# SparkFun_RTK_Express_Plus.net
KiCad netlist of a schematic drawn in EAGLE
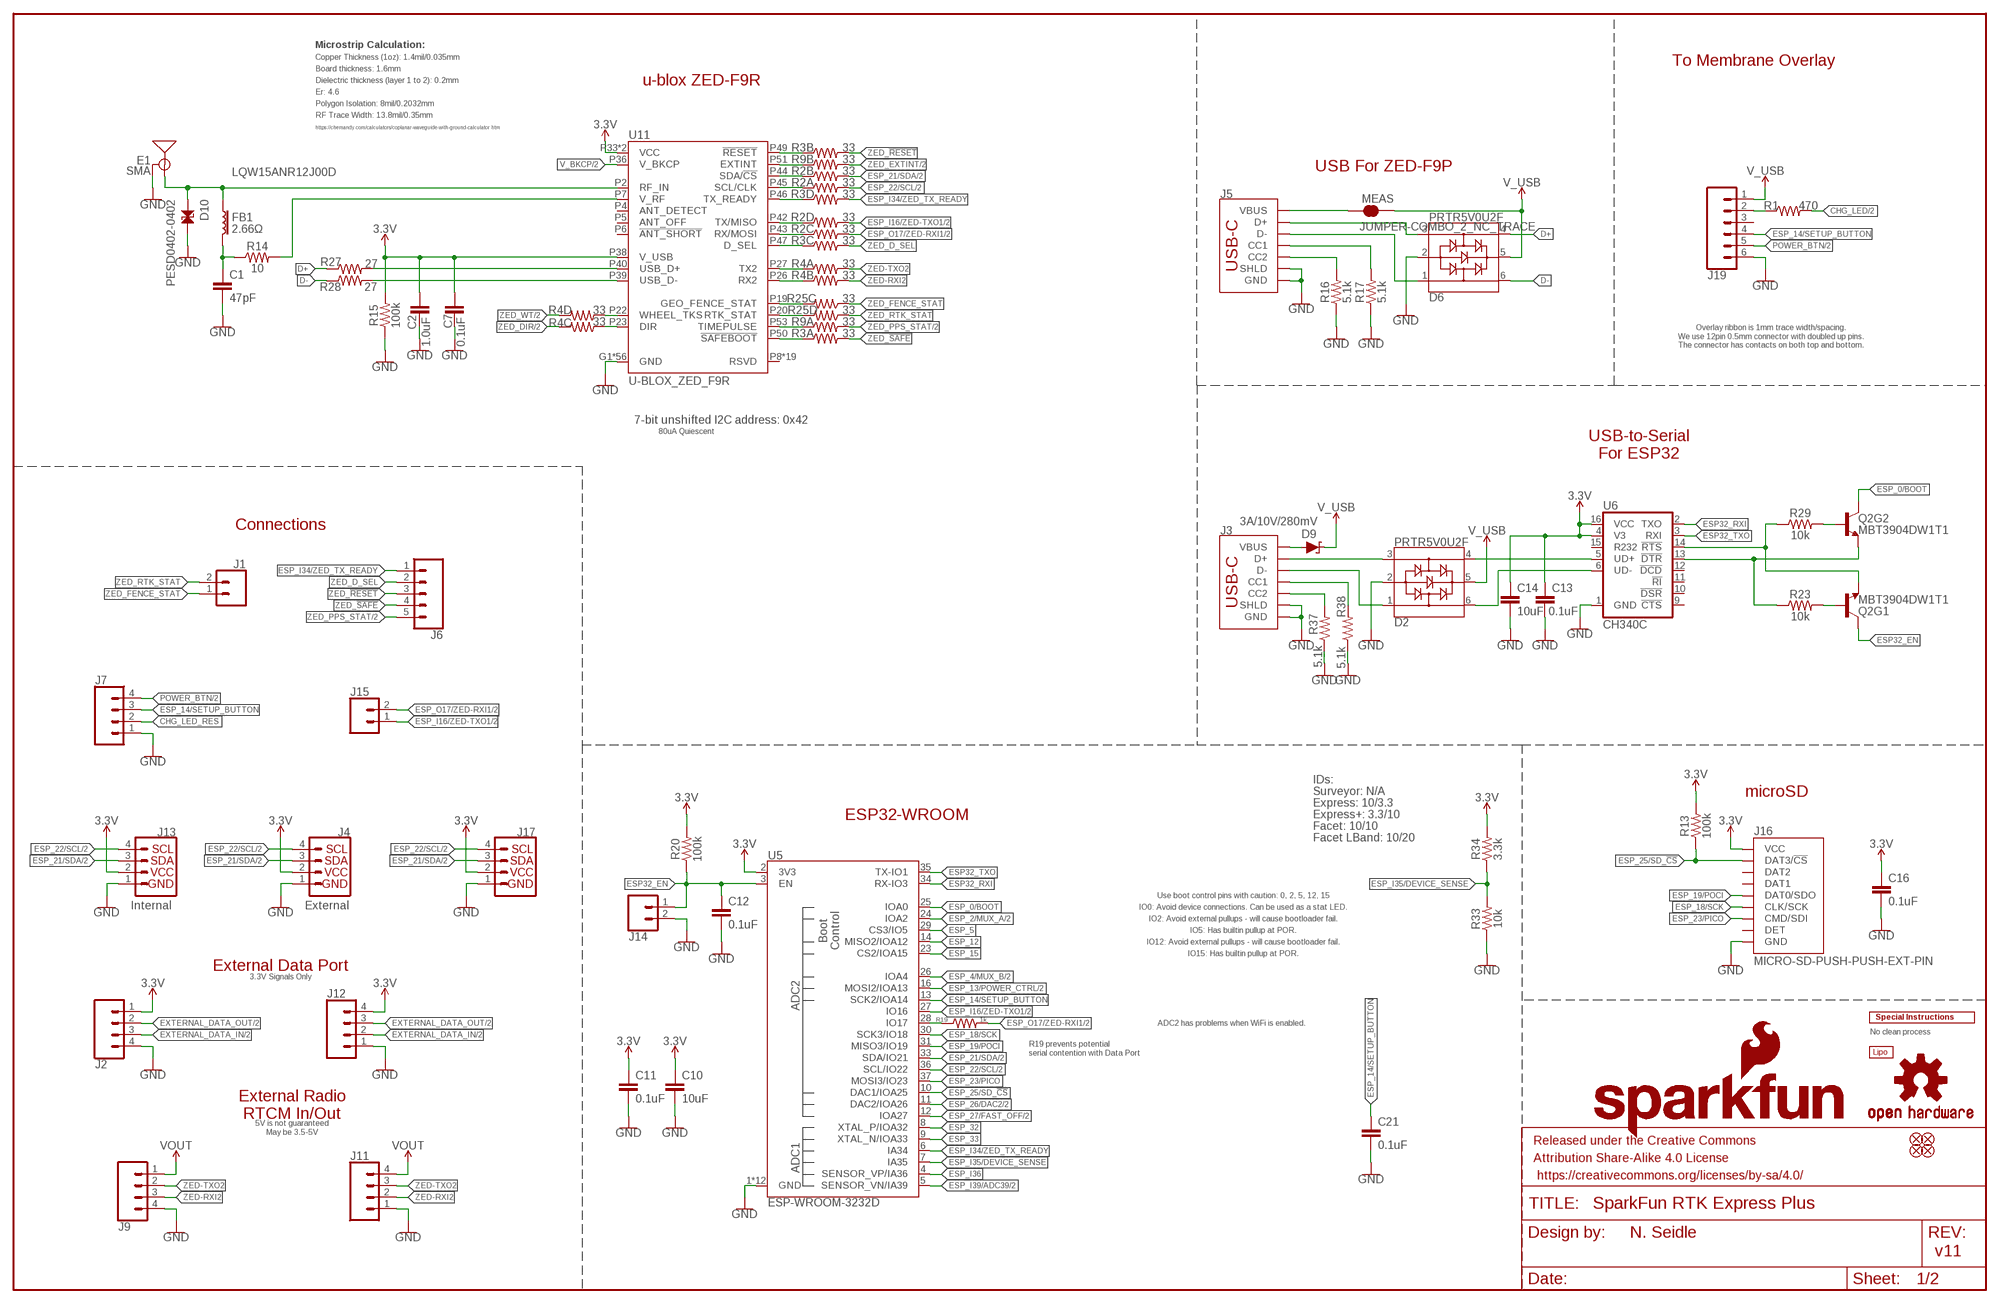
[diagram p0: schematic, sheet 1]
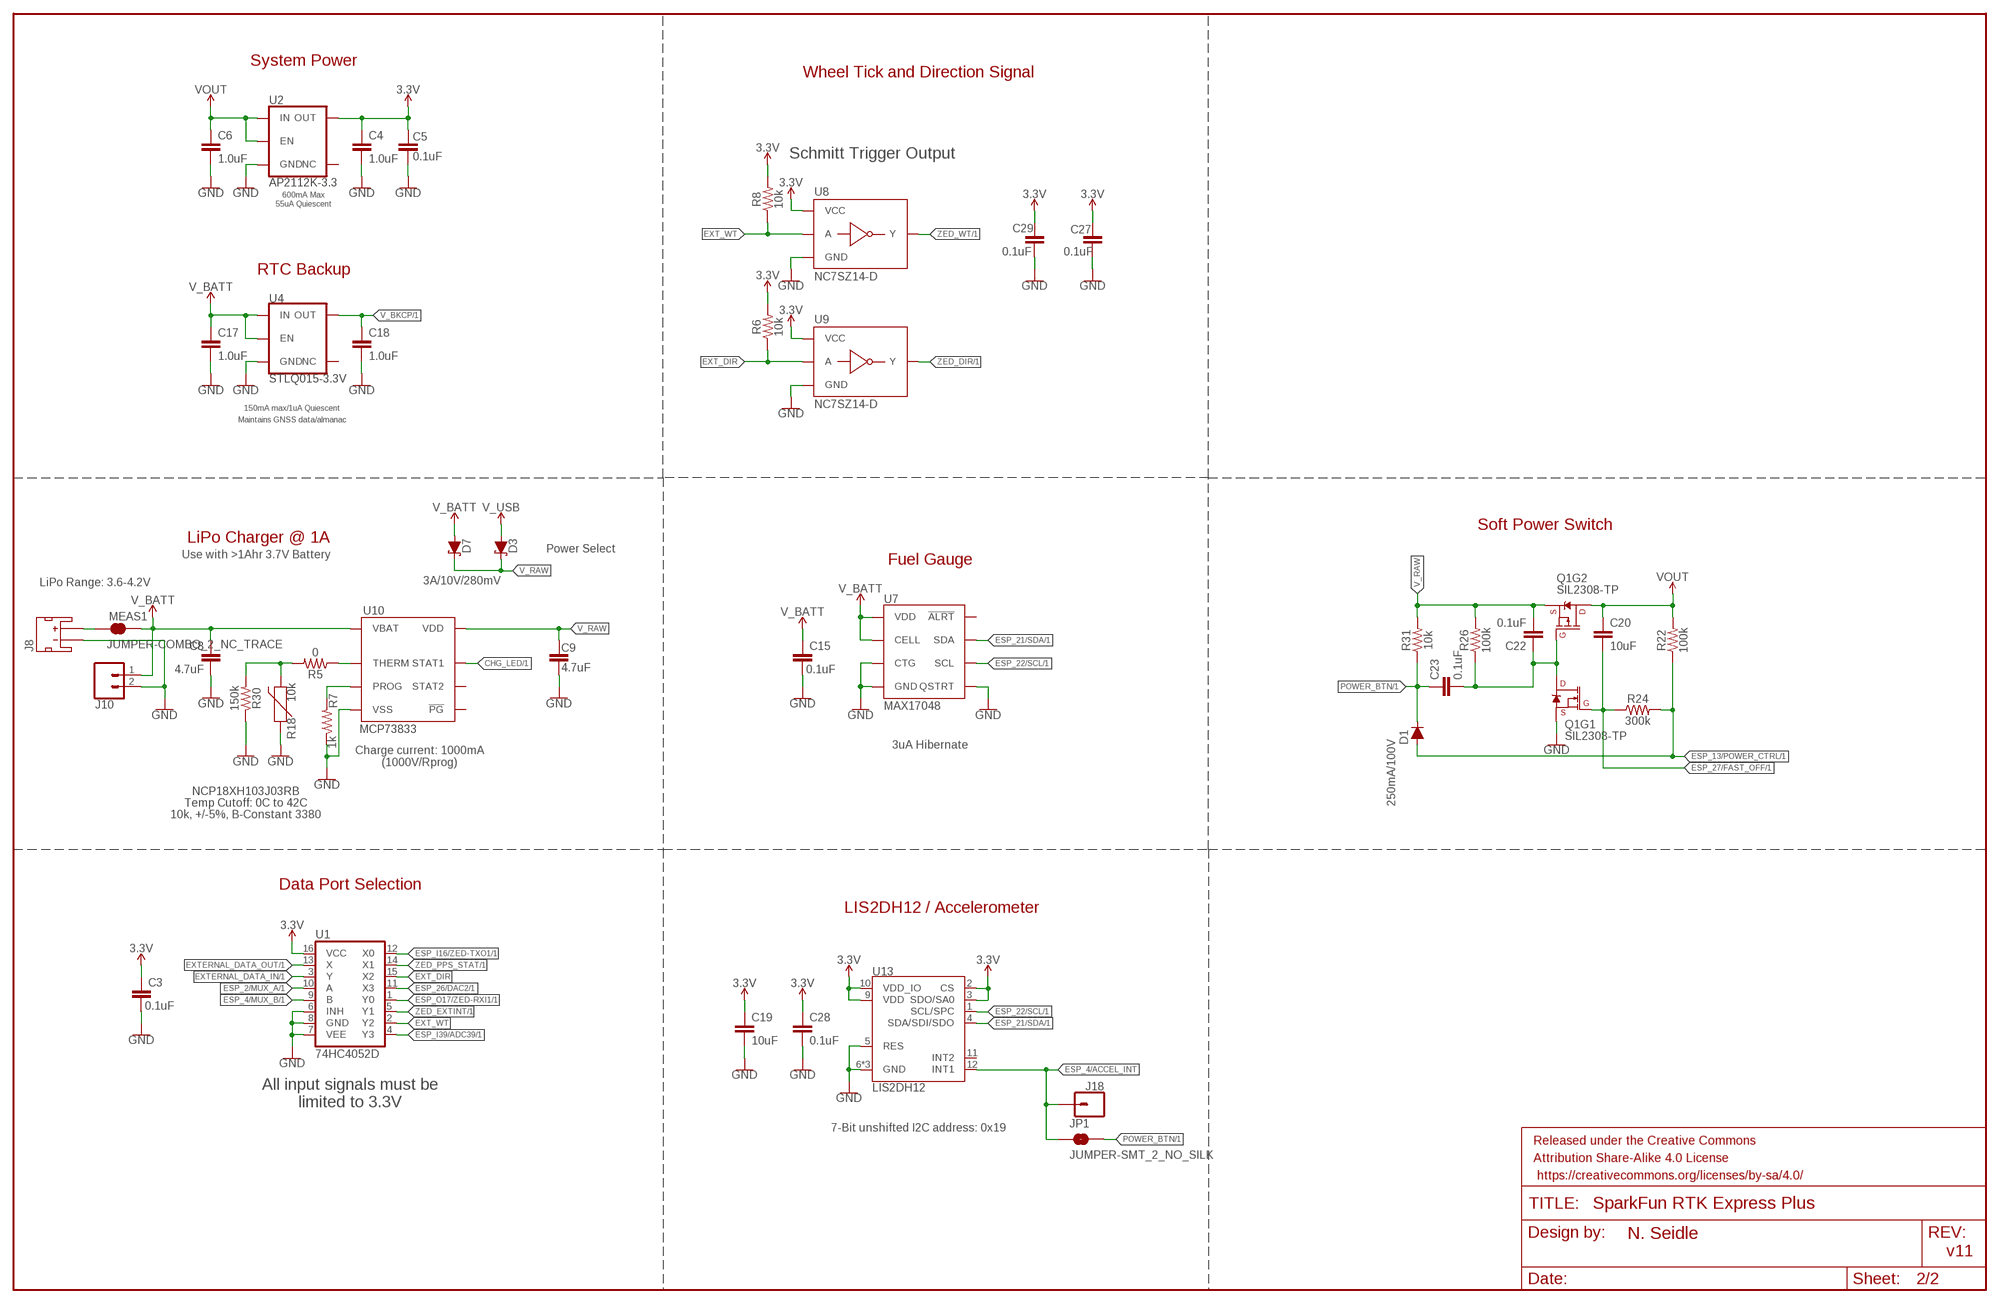
[diagram p1: schematic, sheet 2]

(export (version "E")
  (design (tool "Eeschema 10.0.6"))
  (components
    (comp (ref "C3")
      (value "0.1uF")
      (footprint "eagle-import:0603")
      (libsource (lib "eagle-import") (part "0.1UF-0603-25V-(+80/-20%)"))
    )
    (comp (ref "C4")
      (value "1.0uF")
      (footprint "eagle-import:0603")
      (libsource (lib "eagle-import") (part "1.0UF-0603-16V-10%-X7R"))
    )
    (comp (ref "C5")
      (value "0.1uF")
      (footprint "eagle-import:0603")
      (libsource (lib "eagle-import") (part "0.1UF-0603-25V-5%"))
    )
    (comp (ref "C6")
      (value "1.0uF")
      (footprint "eagle-import:0603")
      (libsource (lib "eagle-import") (part "1.0UF-0603-16V-10%-X7R"))
    )
    (comp (ref "C8")
      (value "4.7uF")
      (footprint "eagle-import:0603")
      (libsource (lib "eagle-import") (part "4.7UF-0603-35V-(20%)"))
    )
    (comp (ref "C9")
      (value "4.7uF")
      (footprint "eagle-import:0603")
      (libsource (lib "eagle-import") (part "4.7UF-0603-35V-(20%)"))
    )
    (comp (ref "C15")
      (value "0.1uF")
      (footprint "eagle-import:0603")
      (libsource (lib "eagle-import") (part "0.1UF-0603-25V-(+80/-20%)"))
    )
    (comp (ref "C17")
      (value "1.0uF")
      (footprint "eagle-import:0603")
      (libsource (lib "eagle-import") (part "1.0UF-0603-16V-10%-X7R"))
    )
    (comp (ref "C18")
      (value "1.0uF")
      (footprint "eagle-import:0603")
      (libsource (lib "eagle-import") (part "1.0UF-0603-16V-10%-X7R"))
    )
    (comp (ref "C19")
      (value "10uF")
      (footprint "eagle-import:0603")
      (libsource (lib "eagle-import") (part "10UF-0603-6.3V-20%"))
    )
    (comp (ref "C20")
      (value "10uF")
      (footprint "eagle-import:0603")
      (libsource (lib "eagle-import") (part "10UF-0603-6.3V-20%"))
    )
    (comp (ref "C22")
      (value "0.1uF")
      (footprint "eagle-import:0603")
      (libsource (lib "eagle-import") (part "0.1UF-0603-25V-5%"))
    )
    (comp (ref "C23")
      (value "0.1uF")
      (footprint "eagle-import:0603")
      (libsource (lib "eagle-import") (part "0.1UF-0603-25V-5%"))
    )
    (comp (ref "C27")
      (value "0.1uF")
      (footprint "eagle-import:0603")
      (libsource (lib "eagle-import") (part "0.1UF-0603-25V-(+80/-20%)"))
    )
    (comp (ref "C28")
      (value "0.1uF")
      (footprint "eagle-import:0603")
      (libsource (lib "eagle-import") (part "0.1UF-0603-25V-(+80/-20%)"))
    )
    (comp (ref "C29")
      (value "0.1uF")
      (footprint "eagle-import:0603")
      (libsource (lib "eagle-import") (part "0.1UF-0603-25V-(+80/-20%)"))
    )
    (comp (ref "D1")
      (value "250mA/100V")
      (footprint "eagle-import:SOD-323")
      (libsource (lib "eagle-import") (part "DIODE-BAS16J"))
    )
    (comp (ref "D3")
      (value "3A/10V/280mV")
      (footprint "eagle-import:SOD-323")
      (libsource (lib "eagle-import") (part "DIODE-SCHOTTKY-BAT60A"))
    )
    (comp (ref "D7")
      (value "3A/10V/280mV")
      (footprint "eagle-import:SOD-323")
      (libsource (lib "eagle-import") (part "DIODE-SCHOTTKY-BAT60A"))
    )
    (comp (ref "FRAME3")
      (value "FRAME-LEDGERNO_FOOTPRINT")
      (footprint "eagle-import:DUMMY")
      (fields (field (name "DESIGNER") "N. Seidle") (field (name "REV") "v10"))
      (libsource (lib "eagle-import") (part "FRAME-LEDGERNO_FOOTPRINT"))
    )
    (comp (ref "J8")
      (value "JST_2MM_MALE")
      (footprint "eagle-import:JST-2-SMD")
      (libsource (lib "eagle-import") (part "JST_2MM_MALE"))
    )
    (comp (ref "J10")
      (value "CONN_021X02_NO_SILK")
      (footprint "eagle-import:1X02_NO_SILK")
      (libsource (lib "eagle-import") (part "CONN_021X02_NO_SILK"))
    )
    (comp (ref "J18")
      (value "CONN_01PTH_NO_SILK_YES_STOP")
      (footprint "eagle-import:1X01_NO_SILK")
      (libsource (lib "eagle-import") (part "CONN_01PTH_NO_SILK_YES_STOP"))
    )
    (comp (ref "JP1")
      (value "JUMPER-SMT_2_NO_SILK")
      (footprint "eagle-import:SMT-JUMPER_2_NO_SILK")
      (libsource (lib "eagle-import") (part "JUMPER-SMT_2_NO_SILK"))
    )
    (comp (ref "MEAS1")
      (value "JUMPER-COMBO_2_NC_TRACE")
      (footprint "eagle-import:COMBO-JUMPER_2_NC_TRACE")
      (libsource (lib "eagle-import") (part "JUMPER-COMBO_2_NC_TRACE"))
    )
    (comp (ref "Q1")
      (value "SIL2308-TP")
      (footprint "eagle-import:SOT26")
      (libsource (lib "eagle-import") (part "MOSFET_COMPLIMENTARY_PAIR-SIL2308"))
    )
    (comp (ref "R5")
      (value "0")
      (footprint "eagle-import:0603")
      (libsource (lib "eagle-import") (part "0OHM-0603-1/10W"))
    )
    (comp (ref "R6")
      (value "10k")
      (footprint "eagle-import:0603")
      (libsource (lib "eagle-import") (part "10KOHM-0603-1/10W-1%"))
    )
    (comp (ref "R7")
      (value "1k")
      (footprint "eagle-import:0603")
      (libsource (lib "eagle-import") (part "1KOHM-0603-1/10W-1%"))
    )
    (comp (ref "R8")
      (value "10k")
      (footprint "eagle-import:0603")
      (libsource (lib "eagle-import") (part "10KOHM-0603-1/10W-1%"))
    )
    (comp (ref "R18")
      (value "10k")
      (footprint "eagle-import:0603")
      (libsource (lib "eagle-import") (part "NTC-THERMISTOR-0603"))
    )
    (comp (ref "R22")
      (value "100k")
      (footprint "eagle-import:0603")
      (libsource (lib "eagle-import") (part "100KOHM-0603-1/10W-1%"))
    )
    (comp (ref "R24")
      (value "300k")
      (footprint "eagle-import:0603")
      (libsource (lib "eagle-import") (part "300KOHM-0603-1/10W-1%"))
    )
    (comp (ref "R26")
      (value "100k")
      (footprint "eagle-import:0603")
      (libsource (lib "eagle-import") (part "100KOHM-0603-1/10W-1%"))
    )
    (comp (ref "R30")
      (value "150k")
      (footprint "eagle-import:0603")
      (libsource (lib "eagle-import") (part "150KOHM-0603-1/10W-1%"))
    )
    (comp (ref "R31")
      (value "10k")
      (footprint "eagle-import:0603")
      (libsource (lib "eagle-import") (part "10KOHM-0603-1/10W-1%"))
    )
    (comp (ref "U1")
      (value "74HC4052D")
      (footprint "eagle-import:SO16")
      (libsource (lib "eagle-import") (part "744052DHC"))
    )
    (comp (ref "U2")
      (value "AP2112K-3.3")
      (footprint "eagle-import:SOT23-5")
      (libsource (lib "eagle-import") (part "V_REG_AP2112K-3.3V"))
    )
    (comp (ref "U4")
      (value "STLQ015-3.3V")
      (footprint "eagle-import:SOT23-5")
      (libsource (lib "eagle-import") (part "STLQ015-3.3V"))
    )
    (comp (ref "U7")
      (value "MAX17048")
      (footprint "eagle-import:DFN-8")
      (libsource (lib "eagle-import") (part "MAX17048DFN8"))
    )
    (comp (ref "U8")
      (value "NC7SZ14-D")
      (footprint "eagle-import:SIP6")
      (libsource (lib "eagle-import") (part "UHS_INVERTER_SCHMITT_TRIGGERSIP6"))
    )
    (comp (ref "U9")
      (value "NC7SZ14-D")
      (footprint "eagle-import:SIP6")
      (libsource (lib "eagle-import") (part "UHS_INVERTER_SCHMITT_TRIGGERSIP6"))
    )
    (comp (ref "U10")
      (value "MCP73833")
      (footprint "eagle-import:DFN-10")
      (libsource (lib "eagle-import") (part "MCP73833"))
    )
    (comp (ref "U13")
      (value "LIS2DH12")
      (footprint "eagle-import:LGA-12-LISDH12")
      (libsource (lib "eagle-import") (part "LIS2DH12"))
    )
    (comp (ref "BT1")
      (value "LIPO-OUTLINE1000")
      (footprint "eagle-import:LIPO-1000")
      (libsource (lib "eagle-import") (part "LIPO-OUTLINE1000"))
    )
    (comp (ref "C1")
      (value "47pF")
      (footprint "eagle-import:0402")
      (libsource (lib "eagle-import") (part "47PF-0402-25V-5%-X7R"))
    )
    (comp (ref "C2")
      (value "1.0uF")
      (footprint "eagle-import:0603")
      (libsource (lib "eagle-import") (part "1.0UF-0603-16V-10%-X7R"))
    )
    (comp (ref "C7")
      (value "0.1uF")
      (footprint "eagle-import:0603")
      (libsource (lib "eagle-import") (part "0.1UF-0603-25V-5%"))
    )
    (comp (ref "C10")
      (value "10uF")
      (footprint "eagle-import:0603")
      (libsource (lib "eagle-import") (part "10UF-0603-6.3V-20%"))
    )
    (comp (ref "C11")
      (value "0.1uF")
      (footprint "eagle-import:0603")
      (libsource (lib "eagle-import") (part "0.1UF-0603-25V-(+80/-20%)"))
    )
    (comp (ref "C12")
      (value "0.1uF")
      (footprint "eagle-import:0603")
      (libsource (lib "eagle-import") (part "0.1UF-0603-25V-(+80/-20%)"))
    )
    (comp (ref "C13")
      (value "0.1uF")
      (footprint "eagle-import:0603")
      (libsource (lib "eagle-import") (part "0.1UF-0603-25V-(+80/-20%)"))
    )
    (comp (ref "C14")
      (value "10uF")
      (footprint "eagle-import:0603")
      (libsource (lib "eagle-import") (part "10UF-0603-6.3V-20%"))
    )
    (comp (ref "C16")
      (value "0.1uF")
      (footprint "eagle-import:0603")
      (libsource (lib "eagle-import") (part "0.1UF-0603-25V-(+80/-20%)"))
    )
    (comp (ref "C21")
      (value "0.1uF")
      (footprint "eagle-import:0603")
      (libsource (lib "eagle-import") (part "0.1UF-0603-25V-(+80/-20%)"))
    )
    (comp (ref "D2")
      (value "PRTR5V0U2F")
      (footprint "eagle-import:SOT886")
      (libsource (lib "eagle-import") (part "PRTR5V0U2F"))
    )
    (comp (ref "D6")
      (value "PRTR5V0U2F")
      (footprint "eagle-import:SOT886")
      (libsource (lib "eagle-import") (part "PRTR5V0U2F"))
    )
    (comp (ref "D9")
      (value "3A/10V/280mV")
      (footprint "eagle-import:SOD-323")
      (libsource (lib "eagle-import") (part "DIODE-SCHOTTKY-BAT60A"))
    )
    (comp (ref "D10")
      (value "PESD0402-0402")
      (footprint "eagle-import:0402")
      (fields
        (field (name "DIGIKEY_PART") "PESD0402-140CT-ND")
        (field (name "MOUSE_PART") "650-PESD0402-140")
      )
      (libsource (lib "eagle-import") (part "PESD0402-0402"))
    )
    (comp (ref "E1")
      (value "SMA")
      (footprint "eagle-import:SMA-EDGE")
      (libsource (lib "eagle-import") (part "ANTENNA-SMA-GROUNDEDEDGE_SMA"))
    )
    (comp (ref "FB1")
      (value "2.66Ω")
      (footprint "eagle-import:0402-TIGHT")
      (libsource (lib "eagle-import") (part "FERRITE_BEAD-0402-2.66Ω-1GHZ"))
    )
    (comp (ref "FRAME2")
      (value "FRAME-LEDGER")
      (footprint "eagle-import:CREATIVE_COMMONS")
      (libsource (lib "eagle-import") (part "FRAME-LEDGER"))
    )
    (comp (ref "J1")
      (value "CONN_021X02_NO_SILK")
      (footprint "eagle-import:1X02_NO_SILK")
      (libsource (lib "eagle-import") (part "CONN_021X02_NO_SILK"))
    )
    (comp (ref "J2")
      (value "CONN_04JST-SMD-LOCKING")
      (footprint "eagle-import:JST-4-SMD-1.25MM-LOCKING")
      (libsource (lib "eagle-import") (part "CONN_04JST-SMD-LOCKING"))
    )
    (comp (ref "J3")
      (value "USB Female Type C Connector")
      (footprint "eagle-import:USB-C-16P_4LAYER-PADS")
      (libsource (lib "eagle-import") (part "USB_C_4-LAYER_PADS"))
    )
    (comp (ref "J4")
      (value "External")
      (footprint "eagle-import:JST04_1MM_RA")
      (libsource (lib "eagle-import") (part "I2C_STANDARDQWIIC"))
    )
    (comp (ref "J5")
      (value "USB Female Type C Connector")
      (footprint "eagle-import:USB-C-16P_4LAYER-PADS")
      (libsource (lib "eagle-import") (part "USB_C_4-LAYER_PADS"))
    )
    (comp (ref "J6")
      (value "CONN_05NO_SILK")
      (footprint "eagle-import:1X05_NO_SILK")
      (libsource (lib "eagle-import") (part "CONN_05NO_SILK"))
    )
    (comp (ref "J7")
      (value "CONN_041X04_NO_SILK_NO_POP")
      (footprint "eagle-import:1X04_NO_SILK")
      (libsource (lib "eagle-import") (part "CONN_041X04_NO_SILK_NO_POP"))
    )
    (comp (ref "J9")
      (value "CONN_04JST-SMD-LOCKING")
      (footprint "eagle-import:JST-4-SMD-1.25MM-LOCKING")
      (libsource (lib "eagle-import") (part "CONN_04JST-SMD-LOCKING"))
    )
    (comp (ref "J11")
      (value "CONN_041X04_NO_SILK_NO_POP")
      (footprint "eagle-import:1X04_NO_SILK")
      (libsource (lib "eagle-import") (part "CONN_041X04_NO_SILK_NO_POP"))
    )
    (comp (ref "J12")
      (value "CONN_041X04_NO_SILK_NO_POP")
      (footprint "eagle-import:1X04_NO_SILK")
      (libsource (lib "eagle-import") (part "CONN_041X04_NO_SILK_NO_POP"))
    )
    (comp (ref "J13")
      (value "Internal")
      (footprint "eagle-import:JST04_1MM_RA")
      (libsource (lib "eagle-import") (part "I2C_STANDARDQWIIC"))
    )
    (comp (ref "J14")
      (value "CONN_021X02_NO_SILK")
      (footprint "eagle-import:1X02_NO_SILK")
      (libsource (lib "eagle-import") (part "CONN_021X02_NO_SILK"))
    )
    (comp (ref "J15")
      (value "CONN_021X02_NO_SILK")
      (footprint "eagle-import:1X02_NO_SILK")
      (libsource (lib "eagle-import") (part "CONN_021X02_NO_SILK"))
    )
    (comp (ref "J16")
      (value "MICRO-SD-PUSH-PUSH-EXT-PIN")
      (footprint "eagle-import:MICROSD-EXTERNALPIN")
      (libsource (lib "eagle-import") (part "MICRO-SD-PUSH-PUSH-EXT-PIN"))
    )
    (comp (ref "J17")
      (value "Qwiic Right Angle")
      (footprint "eagle-import:1X04_NO_SILK")
      (libsource (lib "eagle-import") (part "I2C_STANDARD_NO_SILK"))
    )
    (comp (ref "J19")
      (value "CONN_061MM-LIF")
      (footprint "eagle-import:FPC_6_1MM-LIF")
      (libsource (lib "eagle-import") (part "CONN_061MM-LIF"))
    )
    (comp (ref "JP21")
      (value "FIDUCIALUFIDUCIAL")
      (footprint "eagle-import:FIDUCIAL-MICRO")
      (libsource (lib "eagle-import") (part "FIDUCIALUFIDUCIAL"))
    )
    (comp (ref "JP61")
      (value "FIDUCIALUFIDUCIAL")
      (footprint "eagle-import:FIDUCIAL-MICRO")
      (libsource (lib "eagle-import") (part "FIDUCIALUFIDUCIAL"))
    )
    (comp (ref "JP71")
      (value "FIDUCIALUFIDUCIAL")
      (footprint "eagle-import:FIDUCIAL-MICRO")
      (libsource (lib "eagle-import") (part "FIDUCIALUFIDUCIAL"))
    )
    (comp (ref "JP81")
      (value "FIDUCIALUFIDUCIAL")
      (footprint "eagle-import:FIDUCIAL-MICRO")
      (libsource (lib "eagle-import") (part "FIDUCIALUFIDUCIAL"))
    )
    (comp (ref "LOGO1")
      (value "OSHW-LOGOMINI")
      (footprint "eagle-import:OSHW-LOGO-MINI")
      (libsource (lib "eagle-import") (part "OSHW-LOGOMINI"))
    )
    (comp (ref "LOGO2")
      (value "SFE_LOGO_NAME_FLAME.1_INCH")
      (footprint "eagle-import:SFE_LOGO_NAME_FLAME_.1")
      (libsource (lib "eagle-import") (part "SFE_LOGO_NAME_FLAME.1_INCH"))
    )
    (comp (ref "MEAS")
      (value "JUMPER-COMBO_2_NC_TRACE")
      (footprint "eagle-import:COMBO-JUMPER_2_NC_TRACE")
      (libsource (lib "eagle-import") (part "JUMPER-COMBO_2_NC_TRACE"))
    )
    (comp (ref "Q2")
      (value "MBT3904DW1T1")
      (footprint "eagle-import:SC70-6")
      (libsource (lib "eagle-import") (part "TRANS_NPN_DUAL-MBT3904DW1T1"))
    )
    (comp (ref "R1")
      (value "470")
      (footprint "eagle-import:0603")
      (libsource (lib "eagle-import") (part "470OHM-0603-1/10W-1%"))
    )
    (comp (ref "R2")
      (value "33")
      (footprint "eagle-import:1206_RA")
      (libsource (lib "eagle-import") (part "33OHM_RA-1206-1/16W-5%"))
    )
    (comp (ref "R3")
      (value "33")
      (footprint "eagle-import:1206_RA")
      (libsource (lib "eagle-import") (part "33OHM_RA-1206-1/16W-5%"))
    )
    (comp (ref "R4")
      (value "33")
      (footprint "eagle-import:1206_RA")
      (libsource (lib "eagle-import") (part "33OHM_RA-1206-1/16W-5%"))
    )
    (comp (ref "R9")
      (value "33")
      (footprint "eagle-import:1206_RA")
      (libsource (lib "eagle-import") (part "33OHM_RA-1206-1/16W-5%"))
    )
    (comp (ref "R13")
      (value "100k")
      (footprint "eagle-import:0603")
      (libsource (lib "eagle-import") (part "100KOHM-0603-1/10W-1%"))
    )
    (comp (ref "R14")
      (value "10")
      (footprint "eagle-import:0603")
      (libsource (lib "eagle-import") (part "10OHM-0603-1/10W-1%"))
    )
    (comp (ref "R15")
      (value "100k")
      (footprint "eagle-import:0603")
      (libsource (lib "eagle-import") (part "100KOHM-0603-1/10W-1%"))
    )
    (comp (ref "R16")
      (value "5.1k")
      (footprint "eagle-import:0603")
      (libsource (lib "eagle-import") (part "5.1KOHM5.1KOHM-0603-1/10W-1%"))
    )
    (comp (ref "R17")
      (value "5.1k")
      (footprint "eagle-import:0603")
      (libsource (lib "eagle-import") (part "5.1KOHM5.1KOHM-0603-1/10W-1%"))
    )
    (comp (ref "R19")
      (value "1k")
      (footprint "eagle-import:0603")
      (libsource (lib "eagle-import") (part "1KOHM-0603-1/10W-1%"))
    )
    (comp (ref "R20")
      (value "100k")
      (footprint "eagle-import:0603")
      (libsource (lib "eagle-import") (part "100KOHM-0603-1/10W-1%"))
    )
    (comp (ref "R23")
      (value "10k")
      (footprint "eagle-import:0603")
      (libsource (lib "eagle-import") (part "10KOHM-0603-1/10W-1%"))
    )
    (comp (ref "R25")
      (value "33")
      (footprint "eagle-import:1206_RA")
      (libsource (lib "eagle-import") (part "33OHM_RA-1206-1/16W-5%"))
    )
    (comp (ref "R27")
      (value "27")
      (footprint "eagle-import:0603")
      (libsource (lib "eagle-import") (part "27OHM-0603-1/10W-1%"))
    )
    (comp (ref "R28")
      (value "27")
      (footprint "eagle-import:0603")
      (libsource (lib "eagle-import") (part "27OHM-0603-1/10W-1%"))
    )
    (comp (ref "R29")
      (value "10k")
      (footprint "eagle-import:0603")
      (libsource (lib "eagle-import") (part "10KOHM-0603-1/10W-1%"))
    )
    (comp (ref "R33")
      (value "10k")
      (footprint "eagle-import:0603")
      (libsource (lib "eagle-import") (part "10KOHM-0603-1/10W-1%"))
    )
    (comp (ref "R34")
      (value "3.3k")
      (footprint "eagle-import:0603")
      (libsource (lib "eagle-import") (part "3.3KOHM-0603-1/10W-1%"))
    )
    (comp (ref "R37")
      (value "5.1k")
      (footprint "eagle-import:0603")
      (libsource (lib "eagle-import") (part "5.1KOHM5.1KOHM-0603-1/10W-1%"))
    )
    (comp (ref "R38")
      (value "5.1k")
      (footprint "eagle-import:0603")
      (libsource (lib "eagle-import") (part "5.1KOHM5.1KOHM-0603-1/10W-1%"))
    )
    (comp (ref "U$2")
      (value "SPECIAL_INSTRUCTIONS-ORDERING")
      (footprint "eagle-import:ORDERING_INSTRUCTIONS")
      (libsource (lib "eagle-import") (part "SPECIAL_INSTRUCTIONS-ORDERING"))
    )
    (comp (ref "U5")
      (value "ESP-WROOM-3232D")
      (footprint "eagle-import:ESP-WROOM-32D")
      (libsource (lib "eagle-import") (part "ESP-WROOM-3232D"))
    )
    (comp (ref "U6")
      (value "CH340C")
      (footprint "eagle-import:SO016")
      (libsource (lib "eagle-import") (part "CH340C"))
    )
    (comp (ref "U11")
      (value "U-BLOX_ZED_F9R")
      (footprint "eagle-import:UBLOX_ZED_F9R")
      (libsource (lib "eagle-import") (part "U-BLOX_ZED_F9R"))
    )
  )
  (nets
    (net (code "1") (name "3.3V") (class "Default")
      (node (ref "C10") (pin "1") (pinfunction "1_1") (pintype "passive"))
      (node (ref "C11") (pin "1") (pinfunction "1_1") (pintype "passive"))
      (node (ref "C13") (pin "1") (pinfunction "1_1") (pintype "passive"))
      (node (ref "C14") (pin "1") (pinfunction "1_1") (pintype "passive"))
      (node (ref "C16") (pin "1") (pinfunction "1_1") (pintype "passive"))
      (node (ref "C19") (pin "1") (pinfunction "1_1") (pintype "passive"))
      (node (ref "C2") (pin "1") (pinfunction "1_1") (pintype "passive"))
      (node (ref "C27") (pin "1") (pinfunction "1_1") (pintype "passive"))
      (node (ref "C28") (pin "1") (pinfunction "1_1") (pintype "passive"))
      (node (ref "C29") (pin "1") (pinfunction "1_1") (pintype "passive"))
      (node (ref "C3") (pin "1") (pinfunction "1_1") (pintype "passive"))
      (node (ref "C4") (pin "1") (pinfunction "1_1") (pintype "passive"))
      (node (ref "C5") (pin "2") (pinfunction "2_2") (pintype "passive"))
      (node (ref "C7") (pin "2") (pinfunction "2_2") (pintype "passive"))
      (node (ref "J12") (pin "4") (pinfunction "4_4") (pintype "passive"))
      (node (ref "J13") (pin "2") (pinfunction "2_2") (pintype "power_in"))
      (node (ref "J16") (pin "4") (pinfunction "VCC_4") (pintype "bidirectional"))
      (node (ref "J17") (pin "2") (pinfunction "2_2") (pintype "power_in"))
      (node (ref "J2") (pin "1") (pinfunction "1_1") (pintype "passive"))
      (node (ref "J4") (pin "2") (pinfunction "2_2") (pintype "power_in"))
      (node (ref "R13") (pin "2") (pinfunction "2_2") (pintype "passive"))
      (node (ref "R15") (pin "2") (pinfunction "2_2") (pintype "passive"))
      (node (ref "R20") (pin "2") (pinfunction "2_2") (pintype "passive"))
      (node (ref "R34") (pin "2") (pinfunction "2_2") (pintype "passive"))
      (node (ref "R6") (pin "2") (pinfunction "2_2") (pintype "passive"))
      (node (ref "R8") (pin "2") (pinfunction "2_2") (pintype "passive"))
      (node (ref "U1") (pin "16") (pinfunction "VCC_16") (pintype "power_in"))
      (node (ref "U11") (pin "P33") (pinfunction "VCC_P33") (pintype "power_in"))
      (node (ref "U11") (pin "P34") (pinfunction "VCC_P34") (pintype "power_in"))
      (node (ref "U11") (pin "P38") (pinfunction "V_USB_P38") (pintype "power_in"))
      (node (ref "U13") (pin "10") (pinfunction "VDD_IO_10") (pintype "bidirectional"))
      (node (ref "U13") (pin "2") (pinfunction "CS_2") (pintype "bidirectional"))
      (node (ref "U13") (pin "3") (pinfunction "SDO/SA0_3") (pintype "bidirectional"))
      (node (ref "U13") (pin "9") (pinfunction "VDD_9") (pintype "bidirectional"))
      (node (ref "U2") (pin "5") (pinfunction "OUT_5") (pintype "passive"))
      (node (ref "U5") (pin "2") (pinfunction "3V3_2") (pintype "bidirectional"))
      (node (ref "U6") (pin "16") (pinfunction "VCC_16") (pintype "bidirectional"))
      (node (ref "U6") (pin "4") (pinfunction "V3_4") (pintype "bidirectional"))
      (node (ref "U8") (pin "P6") (pinfunction "VCC_P6") (pintype "power_in"))
      (node (ref "U9") (pin "P6") (pinfunction "VCC_P6") (pintype "power_in"))
    )
    (net (code "2") (name "CHG_LED") (class "Default")
      (node (ref "R1") (pin "2") (pinfunction "2_2") (pintype "passive"))
      (node (ref "U10") (pin "3") (pinfunction "STAT1_3") (pintype "bidirectional"))
    )
    (net (code "3") (name "CHG_LED_RES") (class "Default")
      (node (ref "J19") (pin "2") (pinfunction "2_2") (pintype "passive"))
      (node (ref "J7") (pin "2") (pinfunction "2_2") (pintype "passive"))
      (node (ref "R1") (pin "1") (pinfunction "1_1") (pintype "passive"))
    )
    (net (code "4") (name "D+") (class "Default")
      (node (ref "D6") (pin "4") (pinfunction "4_4") (pintype "bidirectional"))
      (node (ref "R27") (pin "1") (pinfunction "1_1") (pintype "passive"))
    )
    (net (code "5") (name "D-") (class "Default")
      (node (ref "D6") (pin "6") (pinfunction "6_6") (pintype "bidirectional"))
      (node (ref "R28") (pin "1") (pinfunction "1_1") (pintype "passive"))
    )
    (net (code "6") (name "ESP32_EN") (class "Default")
      (node (ref "C12") (pin "1") (pinfunction "1_1") (pintype "passive"))
      (node (ref "J14") (pin "1") (pinfunction "1_1") (pintype "passive"))
      (node (ref "Q2") (pin "3") (pinfunction "C_3") (pintype "passive"))
      (node (ref "R20") (pin "1") (pinfunction "1_1") (pintype "passive"))
      (node (ref "U5") (pin "3") (pinfunction "EN_3") (pintype "bidirectional"))
    )
    (net (code "7") (name "ESP32_RXI") (class "Default")
      (node (ref "U5") (pin "34") (pinfunction "RX-IO3_34") (pintype "bidirectional"))
      (node (ref "U6") (pin "2") (pinfunction "TXO_2") (pintype "bidirectional"))
    )
    (net (code "8") (name "ESP32_TXO") (class "Default")
      (node (ref "U5") (pin "35") (pinfunction "TX-IO1_35") (pintype "bidirectional"))
      (node (ref "U6") (pin "3") (pinfunction "RXI_3") (pintype "bidirectional"))
    )
    (net (code "9") (name "ESP_0{slash}BOOT") (class "Default")
      (node (ref "Q2") (pin "6") (pinfunction "C_6") (pintype "passive"))
      (node (ref "U5") (pin "25") (pinfunction "IOA0_25") (pintype "bidirectional"))
    )
    (net (code "10") (name "ESP_2{slash}MUX_A") (class "Default")
      (node (ref "U1") (pin "10") (pinfunction "A_10") (pintype "input"))
      (node (ref "U5") (pin "24") (pinfunction "IOA2_24") (pintype "bidirectional"))
    )
    (net (code "11") (name "ESP_4{slash}ACCEL_INT") (class "Default")
      (node (ref "J18") (pin "1") (pinfunction "1_1") (pintype "passive"))
      (node (ref "JP1") (pin "1") (pinfunction "1_1") (pintype "passive"))
      (node (ref "U13") (pin "12") (pinfunction "INT1_12") (pintype "bidirectional"))
    )
    (net (code "12") (name "ESP_4{slash}MUX_B") (class "Default")
      (node (ref "U1") (pin "9") (pinfunction "B_9") (pintype "input"))
      (node (ref "U5") (pin "26") (pinfunction "IOA4_26") (pintype "bidirectional"))
    )
    (net (code "13") (name "ESP_5") (class "Default")
      (node (ref "U5") (pin "29") (pinfunction "CS3/IO5_29") (pintype "bidirectional"))
    )
    (net (code "14") (name "ESP_12") (class "Default")
      (node (ref "U5") (pin "14") (pinfunction "MISO2/IOA12_14") (pintype "bidirectional"))
    )
    (net (code "15") (name "ESP_13{slash}POWER_CTRL") (class "Default")
      (node (ref "D1") (pin "A") (pinfunction "A_A") (pintype "passive"))
      (node (ref "R22") (pin "1") (pinfunction "1_1") (pintype "passive"))
      (node (ref "R24") (pin "2") (pinfunction "2_2") (pintype "passive"))
      (node (ref "U5") (pin "16") (pinfunction "MOSI2/IOA13_16") (pintype "bidirectional"))
    )
    (net (code "16") (name "ESP_14{slash}SETUP_BUTTON") (class "Default")
      (node (ref "C21") (pin "1") (pinfunction "1_1") (pintype "passive"))
      (node (ref "J19") (pin "4") (pinfunction "4_4") (pintype "passive"))
      (node (ref "J7") (pin "3") (pinfunction "3_3") (pintype "passive"))
      (node (ref "U5") (pin "13") (pinfunction "SCK2/IOA14_13") (pintype "bidirectional"))
    )
    (net (code "17") (name "ESP_15") (class "Default")
      (node (ref "U5") (pin "23") (pinfunction "CS2/IOA15_23") (pintype "bidirectional"))
    )
    (net (code "18") (name "ESP_18{slash}SCK") (class "Default")
      (node (ref "J16") (pin "5") (pinfunction "CLK/SCK_5") (pintype "bidirectional"))
      (node (ref "U5") (pin "30") (pinfunction "SCK3/IO18_30") (pintype "bidirectional"))
    )
    (net (code "19") (name "ESP_19{slash}POCI") (class "Default")
      (node (ref "J16") (pin "7") (pinfunction "DAT0/SDO_7") (pintype "bidirectional"))
      (node (ref "U5") (pin "31") (pinfunction "MISO3/IO19_31") (pintype "bidirectional"))
    )
    (net (code "20") (name "ESP_21{slash}SDA") (class "Default")
      (node (ref "J13") (pin "3") (pinfunction "3_3") (pintype "passive"))
      (node (ref "J17") (pin "3") (pinfunction "3_3") (pintype "passive"))
      (node (ref "J4") (pin "3") (pinfunction "3_3") (pintype "passive"))
      (node (ref "R2") (pin "P7") (pinfunction "2_P7") (pintype "passive"))
      (node (ref "U13") (pin "4") (pinfunction "SDA/SDI/SDO_4") (pintype "bidirectional"))
      (node (ref "U5") (pin "33") (pinfunction "SDA/IO21_33") (pintype "bidirectional"))
      (node (ref "U7") (pin "8") (pinfunction "SDA_8") (pintype "input"))
    )
    (net (code "21") (name "ESP_22{slash}SCL") (class "Default")
      (node (ref "J13") (pin "4") (pinfunction "4_4") (pintype "passive"))
      (node (ref "J17") (pin "4") (pinfunction "4_4") (pintype "passive"))
      (node (ref "J4") (pin "4") (pinfunction "4_4") (pintype "passive"))
      (node (ref "R2") (pin "P8") (pinfunction "2_P8") (pintype "passive"))
      (node (ref "U13") (pin "1") (pinfunction "SCL/SPC_1") (pintype "bidirectional"))
      (node (ref "U5") (pin "36") (pinfunction "SCL/IO22_36") (pintype "bidirectional"))
      (node (ref "U7") (pin "7") (pinfunction "SCL_7") (pintype "output"))
    )
    (net (code "22") (name "ESP_23{slash}PICO") (class "Default")
      (node (ref "J16") (pin "3") (pinfunction "CMD/SDI_3") (pintype "bidirectional"))
      (node (ref "U5") (pin "37") (pinfunction "MOSI3/IO23_37") (pintype "bidirectional"))
    )
    (net (code "23") (name "ESP_25{slash}SD_~{CS}") (class "Default")
      (node (ref "J16") (pin "2") (pinfunction "DAT3/~{CS}_2") (pintype "bidirectional"))
      (node (ref "R13") (pin "1") (pinfunction "1_1") (pintype "passive"))
      (node (ref "U5") (pin "10") (pinfunction "DAC1/IOA25_10") (pintype "bidirectional"))
    )
    (net (code "24") (name "ESP_26{slash}DAC2") (class "Default")
      (node (ref "U1") (pin "11") (pinfunction "X3_11") (pintype "bidirectional"))
      (node (ref "U5") (pin "11") (pinfunction "DAC2/IOA26_11") (pintype "bidirectional"))
    )
    (net (code "25") (name "ESP_27{slash}FAST_OFF") (class "Default")
      (node (ref "C20") (pin "2") (pinfunction "2_2") (pintype "passive"))
      (node (ref "Q1") (pin "G1") (pinfunction "G_G1") (pintype "bidirectional"))
      (node (ref "R24") (pin "1") (pinfunction "1_1") (pintype "passive"))
      (node (ref "U5") (pin "12") (pinfunction "IOA27_12") (pintype "bidirectional"))
    )
    (net (code "26") (name "ESP_32") (class "Default")
      (node (ref "U5") (pin "8") (pinfunction "XTAL_P/IOA32_8") (pintype "bidirectional"))
    )
    (net (code "27") (name "ESP_33") (class "Default")
      (node (ref "U5") (pin "9") (pinfunction "XTAL_N/IOA33_9") (pintype "bidirectional"))
    )
    (net (code "28") (name "ESP_I16{slash}ZED-TXO1") (class "Default")
      (node (ref "J15") (pin "1") (pinfunction "1_1") (pintype "passive"))
      (node (ref "R2") (pin "P5") (pinfunction "2_P5") (pintype "passive"))
      (node (ref "U1") (pin "12") (pinfunction "X0_12") (pintype "bidirectional"))
      (node (ref "U5") (pin "27") (pinfunction "IO16_27") (pintype "bidirectional"))
    )
    (net (code "29") (name "ESP_I34{slash}ZED_TX_READY") (class "Default")
      (node (ref "J6") (pin "1") (pinfunction "1_1") (pintype "passive"))
      (node (ref "R3") (pin "P5") (pinfunction "2_P5") (pintype "passive"))
      (node (ref "U5") (pin "6") (pinfunction "IA34_6") (pintype "bidirectional"))
    )
    (net (code "30") (name "ESP_I35{slash}DEVICE_SENSE") (class "Default")
      (node (ref "R33") (pin "2") (pinfunction "2_2") (pintype "passive"))
      (node (ref "R34") (pin "1") (pinfunction "1_1") (pintype "passive"))
      (node (ref "U5") (pin "7") (pinfunction "IA35_7") (pintype "bidirectional"))
    )
    (net (code "31") (name "ESP_I36") (class "Default")
      (node (ref "U5") (pin "4") (pinfunction "SENSOR_VP/IA36_4") (pintype "bidirectional"))
    )
    (net (code "32") (name "ESP_I39{slash}ADC39") (class "Default")
      (node (ref "U1") (pin "4") (pinfunction "Y3_4") (pintype "bidirectional"))
      (node (ref "U5") (pin "5") (pinfunction "SENSOR_VN/IA39_5") (pintype "bidirectional"))
    )
    (net (code "33") (name "ESP_O17{slash}ZED-RXI1") (class "Default")
      (node (ref "J15") (pin "2") (pinfunction "2_2") (pintype "passive"))
      (node (ref "R19") (pin "2") (pinfunction "2_2") (pintype "passive"))
      (node (ref "R2") (pin "P6") (pinfunction "2_P6") (pintype "passive"))
      (node (ref "U1") (pin "1") (pinfunction "Y0_1") (pintype "bidirectional"))
    )
    (net (code "34") (name "EXTERNAL_DATA_IN") (class "Default")
      (node (ref "J12") (pin "2") (pinfunction "2_2") (pintype "passive"))
      (node (ref "J2") (pin "3") (pinfunction "3_3") (pintype "passive"))
      (node (ref "U1") (pin "3") (pinfunction "Y_3") (pintype "bidirectional"))
    )
    (net (code "35") (name "EXTERNAL_DATA_OUT") (class "Default")
      (node (ref "J12") (pin "3") (pinfunction "3_3") (pintype "passive"))
      (node (ref "J2") (pin "2") (pinfunction "2_2") (pintype "passive"))
      (node (ref "U1") (pin "13") (pinfunction "X_13") (pintype "bidirectional"))
    )
    (net (code "36") (name "EXT_DIR") (class "Default")
      (node (ref "R6") (pin "1") (pinfunction "1_1") (pintype "passive"))
      (node (ref "U1") (pin "15") (pinfunction "X2_15") (pintype "bidirectional"))
      (node (ref "U9") (pin "P2") (pinfunction "A_P2") (pintype "input"))
    )
    (net (code "37") (name "EXT_WT") (class "Default")
      (node (ref "R8") (pin "1") (pinfunction "1_1") (pintype "passive"))
      (node (ref "U1") (pin "2") (pinfunction "Y2_2") (pintype "bidirectional"))
      (node (ref "U8") (pin "P2") (pinfunction "A_P2") (pintype "input"))
    )
    (net (code "38") (name "GND") (class "Default")
      (node (ref "C1") (pin "2") (pinfunction "2_2") (pintype "passive"))
      (node (ref "C10") (pin "2") (pinfunction "2_2") (pintype "passive"))
      (node (ref "C11") (pin "2") (pinfunction "2_2") (pintype "passive"))
      (node (ref "C12") (pin "2") (pinfunction "2_2") (pintype "passive"))
      (node (ref "C13") (pin "2") (pinfunction "2_2") (pintype "passive"))
      (node (ref "C14") (pin "2") (pinfunction "2_2") (pintype "passive"))
      (node (ref "C15") (pin "2") (pinfunction "2_2") (pintype "passive"))
      (node (ref "C16") (pin "2") (pinfunction "2_2") (pintype "passive"))
      (node (ref "C17") (pin "2") (pinfunction "2_2") (pintype "passive"))
      (node (ref "C18") (pin "2") (pinfunction "2_2") (pintype "passive"))
      (node (ref "C19") (pin "2") (pinfunction "2_2") (pintype "passive"))
      (node (ref "C2") (pin "2") (pinfunction "2_2") (pintype "passive"))
      (node (ref "C21") (pin "2") (pinfunction "2_2") (pintype "passive"))
      (node (ref "C27") (pin "2") (pinfunction "2_2") (pintype "passive"))
      (node (ref "C28") (pin "2") (pinfunction "2_2") (pintype "passive"))
      (node (ref "C29") (pin "2") (pinfunction "2_2") (pintype "passive"))
      (node (ref "C3") (pin "2") (pinfunction "2_2") (pintype "passive"))
      (node (ref "C4") (pin "2") (pinfunction "2_2") (pintype "passive"))
      (node (ref "C5") (pin "1") (pinfunction "1_1") (pintype "passive"))
      (node (ref "C6") (pin "2") (pinfunction "2_2") (pintype "passive"))
      (node (ref "C7") (pin "1") (pinfunction "1_1") (pintype "passive"))
      (node (ref "C8") (pin "2") (pinfunction "2_2") (pintype "passive"))
      (node (ref "C9") (pin "2") (pinfunction "2_2") (pintype "passive"))
      (node (ref "D10") (pin "2") (pinfunction "2_2") (pintype "bidirectional"))
      (node (ref "D2") (pin "2") (pinfunction "2_2") (pintype "power_in"))
      (node (ref "D6") (pin "2") (pinfunction "2_2") (pintype "power_in"))
      (node (ref "E1") (pin "GND@0") (pinfunction "GND_GND@0") (pintype "bidirectional"))
      (node (ref "E1") (pin "GND@1") (pinfunction "GND_GND@1") (pintype "bidirectional"))
      (node (ref "E1") (pin "GND@2") (pinfunction "GND_GND@2") (pintype "bidirectional"))
      (node (ref "E1") (pin "GND@3") (pinfunction "GND_GND@3") (pintype "bidirectional"))
      (node (ref "J10") (pin "2") (pinfunction "2_2") (pintype "passive"))
      (node (ref "J11") (pin "1") (pinfunction "1_1") (pintype "passive"))
      (node (ref "J12") (pin "1") (pinfunction "1_1") (pintype "passive"))
      (node (ref "J13") (pin "1") (pinfunction "1_1") (pintype "power_in"))
      (node (ref "J14") (pin "2") (pinfunction "2_2") (pintype "passive"))
      (node (ref "J16") (pin "10") (pinfunction "GND_10") (pintype "bidirectional"))
      (node (ref "J16") (pin "11") (pinfunction "GND_11") (pintype "bidirectional"))
      (node (ref "J16") (pin "12") (pinfunction "GND_12") (pintype "bidirectional"))
      (node (ref "J16") (pin "13") (pinfunction "GND_13") (pintype "bidirectional"))
      (node (ref "J16") (pin "6") (pinfunction "GND_6") (pintype "bidirectional"))
      (node (ref "J17") (pin "1") (pinfunction "1_1") (pintype "power_in"))
      (node (ref "J19") (pin "6") (pinfunction "6_6") (pintype "passive"))
      (node (ref "J2") (pin "4") (pinfunction "4_4") (pintype "passive"))
      (node (ref "J3") (pin "GND") (pinfunction "GND_GND") (pintype "bidirectional"))
      (node (ref "J3") (pin "GND2") (pinfunction "GND_GND2") (pintype "bidirectional"))
      (node (ref "J3") (pin "SHLD1") (pinfunction "SHLD_SHLD1") (pintype "bidirectional"))
      (node (ref "J3") (pin "SHLD2") (pinfunction "SHLD_SHLD2") (pintype "bidirectional"))
      (node (ref "J3") (pin "SHLD3") (pinfunction "SHLD_SHLD3") (pintype "bidirectional"))
      (node (ref "J3") (pin "SHLD4") (pinfunction "SHLD_SHLD4") (pintype "bidirectional"))
      (node (ref "J4") (pin "1") (pinfunction "1_1") (pintype "power_in"))
      (node (ref "J5") (pin "GND") (pinfunction "GND_GND") (pintype "bidirectional"))
      (node (ref "J5") (pin "GND2") (pinfunction "GND_GND2") (pintype "bidirectional"))
      (node (ref "J5") (pin "SHLD1") (pinfunction "SHLD_SHLD1") (pintype "bidirectional"))
      (node (ref "J5") (pin "SHLD2") (pinfunction "SHLD_SHLD2") (pintype "bidirectional"))
      (node (ref "J5") (pin "SHLD3") (pinfunction "SHLD_SHLD3") (pintype "bidirectional"))
      (node (ref "J5") (pin "SHLD4") (pinfunction "SHLD_SHLD4") (pintype "bidirectional"))
      (node (ref "J7") (pin "1") (pinfunction "1_1") (pintype "passive"))
      (node (ref "J8") (pin "1") (pinfunction "-_1") (pintype "bidirectional"))
      (node (ref "J9") (pin "4") (pinfunction "4_4") (pintype "passive"))
      (node (ref "Q1") (pin "S1") (pinfunction "S_S1") (pintype "bidirectional"))
      (node (ref "R15") (pin "1") (pinfunction "1_1") (pintype "passive"))
      (node (ref "R16") (pin "1") (pinfunction "1_1") (pintype "passive"))
      (node (ref "R17") (pin "1") (pinfunction "1_1") (pintype "passive"))
      (node (ref "R18") (pin "1") (pinfunction "1_1") (pintype "bidirectional"))
      (node (ref "R30") (pin "1") (pinfunction "1_1") (pintype "passive"))
      (node (ref "R33") (pin "1") (pinfunction "1_1") (pintype "passive"))
      (node (ref "R37") (pin "1") (pinfunction "1_1") (pintype "passive"))
      (node (ref "R38") (pin "1") (pinfunction "1_1") (pintype "passive"))
      (node (ref "R7") (pin "1") (pinfunction "1_1") (pintype "passive"))
      (node (ref "U1") (pin "6") (pinfunction "INH_6") (pintype "input"))
      (node (ref "U1") (pin "7") (pinfunction "VEE_7") (pintype "power_in"))
      (node (ref "U1") (pin "8") (pinfunction "GND_8") (pintype "power_in"))
      (node (ref "U10") (pin "11") (pinfunction "VSS_11") (pintype "bidirectional"))
      (node (ref "U10") (pin "5") (pinfunction "VSS_5") (pintype "bidirectional"))
      (node (ref "U11") (pin "G1") (pinfunction "GND_G1") (pintype "power_in"))
      (node (ref "U11") (pin "G10") (pinfunction "GND_G10") (pintype "power_in"))
      (node (ref "U11") (pin "G11") (pinfunction "GND_G11") (pintype "power_in"))
      (node (ref "U11") (pin "G12") (pinfunction "GND_G12") (pintype "power_in"))
      (node (ref "U11") (pin "G13") (pinfunction "GND_G13") (pintype "power_in"))
      (node (ref "U11") (pin "G14") (pinfunction "GND_G14") (pintype "power_in"))
      (node (ref "U11") (pin "G15") (pinfunction "GND_G15") (pintype "power_in"))
      (node (ref "U11") (pin "G16") (pinfunction "GND_G16") (pintype "power_in"))
      (node (ref "U11") (pin "G17") (pinfunction "GND_G17") (pintype "power_in"))
      (node (ref "U11") (pin "G18") (pinfunction "GND_G18") (pintype "power_in"))
      (node (ref "U11") (pin "G19") (pinfunction "GND_G19") (pintype "power_in"))
      (node (ref "U11") (pin "G2") (pinfunction "GND_G2") (pintype "power_in"))
      (node (ref "U11") (pin "G20") (pinfunction "GND_G20") (pintype "power_in"))
      (node (ref "U11") (pin "G21") (pinfunction "GND_G21") (pintype "power_in"))
      (node (ref "U11") (pin "G22") (pinfunction "GND_G22") (pintype "power_in"))
      (node (ref "U11") (pin "G23") (pinfunction "GND_G23") (pintype "power_in"))
      (node (ref "U11") (pin "G24") (pinfunction "GND_G24") (pintype "power_in"))
      (node (ref "U11") (pin "G25") (pinfunction "GND_G25") (pintype "power_in"))
      (node (ref "U11") (pin "G26") (pinfunction "GND_G26") (pintype "power_in"))
      (node (ref "U11") (pin "G27") (pinfunction "GND_G27") (pintype "power_in"))
      (node (ref "U11") (pin "G28") (pinfunction "GND_G28") (pintype "power_in"))
      (node (ref "U11") (pin "G29") (pinfunction "GND_G29") (pintype "power_in"))
      (node (ref "U11") (pin "G3") (pinfunction "GND_G3") (pintype "power_in"))
      (node (ref "U11") (pin "G30") (pinfunction "GND_G30") (pintype "power_in"))
      (node (ref "U11") (pin "G31") (pinfunction "GND_G31") (pintype "power_in"))
      (node (ref "U11") (pin "G32") (pinfunction "GND_G32") (pintype "power_in"))
      (node (ref "U11") (pin "G33") (pinfunction "GND_G33") (pintype "power_in"))
      (node (ref "U11") (pin "G34") (pinfunction "GND_G34") (pintype "power_in"))
      (node (ref "U11") (pin "G35") (pinfunction "GND_G35") (pintype "power_in"))
      (node (ref "U11") (pin "G36") (pinfunction "GND_G36") (pintype "power_in"))
      (node (ref "U11") (pin "G37") (pinfunction "GND_G37") (pintype "power_in"))
      (node (ref "U11") (pin "G38") (pinfunction "GND_G38") (pintype "power_in"))
      (node (ref "U11") (pin "G39") (pinfunction "GND_G39") (pintype "power_in"))
      (node (ref "U11") (pin "G4") (pinfunction "GND_G4") (pintype "power_in"))
      (node (ref "U11") (pin "G40") (pinfunction "GND_G40") (pintype "power_in"))
      (node (ref "U11") (pin "G41") (pinfunction "GND_G41") (pintype "power_in"))
      (node (ref "U11") (pin "G42") (pinfunction "GND_G42") (pintype "power_in"))
      (node (ref "U11") (pin "G43") (pinfunction "GND_G43") (pintype "power_in"))
      (node (ref "U11") (pin "G44") (pinfunction "GND_G44") (pintype "power_in"))
      (node (ref "U11") (pin "G45") (pinfunction "GND_G45") (pintype "power_in"))
      (node (ref "U11") (pin "G46") (pinfunction "GND_G46") (pintype "power_in"))
      (node (ref "U11") (pin "G47") (pinfunction "GND_G47") (pintype "power_in"))
      (node (ref "U11") (pin "G48") (pinfunction "GND_G48") (pintype "power_in"))
      (node (ref "U11") (pin "G5") (pinfunction "GND_G5") (pintype "power_in"))
      (node (ref "U11") (pin "G6") (pinfunction "GND_G6") (pintype "power_in"))
      (node (ref "U11") (pin "G7") (pinfunction "GND_G7") (pintype "power_in"))
      (node (ref "U11") (pin "G8") (pinfunction "GND_G8") (pintype "power_in"))
      (node (ref "U11") (pin "G9") (pinfunction "GND_G9") (pintype "power_in"))
      (node (ref "U11") (pin "P1") (pinfunction "GND_P1") (pintype "power_in"))
      (node (ref "U11") (pin "P12") (pinfunction "GND_P12") (pintype "power_in"))
      (node (ref "U11") (pin "P14") (pinfunction "GND_P14") (pintype "power_in"))
      (node (ref "U11") (pin "P3") (pinfunction "GND_P3") (pintype "power_in"))
      (node (ref "U11") (pin "P32") (pinfunction "GND_P32") (pintype "power_in"))
      (node (ref "U11") (pin "P37") (pinfunction "GND_P37") (pintype "power_in"))
      (node (ref "U11") (pin "P41") (pinfunction "GND_P41") (pintype "power_in"))
      (node (ref "U11") (pin "P48") (pinfunction "GND_P48") (pintype "power_in"))
      (node (ref "U13") (pin "5") (pinfunction "RES_5") (pintype "bidirectional"))
      (node (ref "U13") (pin "6") (pinfunction "GND_6") (pintype "bidirectional"))
      (node (ref "U13") (pin "7") (pinfunction "GND_7") (pintype "bidirectional"))
      (node (ref "U13") (pin "8") (pinfunction "GND_8") (pintype "bidirectional"))
      (node (ref "U2") (pin "2") (pinfunction "GND_2") (pintype "input"))
      (node (ref "U4") (pin "2") (pinfunction "GND_2") (pintype "input"))
      (node (ref "U5") (pin "1") (pinfunction "GND_1") (pintype "bidirectional"))
      (node (ref "U5") (pin "15") (pinfunction "GND_15") (pintype "bidirectional"))
      (node (ref "U5") (pin "38") (pinfunction "GND_38") (pintype "bidirectional"))
      (node (ref "U5") (pin "GND") (pinfunction "GND_GND") (pintype "bidirectional"))
      (node (ref "U5") (pin "GNDT1") (pinfunction "GND_GNDT1") (pintype "bidirectional"))
      (node (ref "U5") (pin "GNDT2") (pinfunction "GND_GNDT2") (pintype "bidirectional"))
      (node (ref "U5") (pin "GNDT3") (pinfunction "GND_GNDT3") (pintype "bidirectional"))
      (node (ref "U5") (pin "GNDT4") (pinfunction "GND_GNDT4") (pintype "bidirectional"))
      (node (ref "U5") (pin "GNDT5") (pinfunction "GND_GNDT5") (pintype "bidirectional"))
      (node (ref "U5") (pin "GNDT6") (pinfunction "GND_GNDT6") (pintype "bidirectional"))
      (node (ref "U5") (pin "GNDT7") (pinfunction "GND_GNDT7") (pintype "bidirectional"))
      (node (ref "U5") (pin "GNDT8") (pinfunction "GND_GNDT8") (pintype "bidirectional"))
      (node (ref "U6") (pin "1") (pinfunction "GND_1") (pintype "bidirectional"))
      (node (ref "U7") (pin "1") (pinfunction "CTG_1") (pintype "input"))
      (node (ref "U7") (pin "4") (pinfunction "GND_4") (pintype "bidirectional"))
      (node (ref "U7") (pin "6") (pinfunction "QSTRT_6") (pintype "bidirectional"))
      (node (ref "U7") (pin "9") (pinfunction "GND_9") (pintype "bidirectional"))
      (node (ref "U8") (pin "P3") (pinfunction "GND_P3") (pintype "power_in"))
      (node (ref "U9") (pin "P3") (pinfunction "GND_P3") (pintype "power_in"))
    )
    (net (code "39") (name "Net-(C1-Pad1)") (class "Default")
      (node (ref "C1") (pin "1") (pinfunction "1_1") (pintype "passive"))
      (node (ref "FB1") (pin "2") (pinfunction "2_2") (pintype "passive"))
      (node (ref "R14") (pin "1") (pinfunction "1_1") (pintype "passive"))
    )
    (net (code "40") (name "Net-(D2-Pad1)") (class "Default")
      (node (ref "D2") (pin "1") (pinfunction "1_1") (pintype "bidirectional"))
      (node (ref "J3") (pin "A7") (pinfunction "D-_A7") (pintype "bidirectional"))
      (node (ref "J3") (pin "B7") (pinfunction "D-_B7") (pintype "bidirectional"))
    )
    (net (code "41") (name "Net-(D2-Pad3)") (class "Default")
      (node (ref "D2") (pin "3") (pinfunction "3_3") (pintype "bidirectional"))
      (node (ref "J3") (pin "A6") (pinfunction "D+_A6") (pintype "bidirectional"))
      (node (ref "J3") (pin "B6") (pinfunction "D+_B6") (pintype "bidirectional"))
    )
    (net (code "42") (name "Net-(D6-Pad1)") (class "Default")
      (node (ref "D6") (pin "1") (pinfunction "1_1") (pintype "bidirectional"))
      (node (ref "J5") (pin "A7") (pinfunction "D-_A7") (pintype "bidirectional"))
      (node (ref "J5") (pin "B7") (pinfunction "D-_B7") (pintype "bidirectional"))
    )
    (net (code "43") (name "Net-(D6-Pad3)") (class "Default")
      (node (ref "D6") (pin "3") (pinfunction "3_3") (pintype "bidirectional"))
      (node (ref "J5") (pin "A6") (pinfunction "D+_A6") (pintype "bidirectional"))
      (node (ref "J5") (pin "B6") (pinfunction "D+_B6") (pintype "bidirectional"))
    )
    (net (code "44") (name "Net-(D9-PadA)") (class "Default")
      (node (ref "D9") (pin "A") (pinfunction "A_A") (pintype "passive"))
      (node (ref "J3") (pin "VBUS1") (pinfunction "VBUS_VBUS1") (pintype "bidirectional"))
      (node (ref "J3") (pin "VBUS2") (pinfunction "VBUS_VBUS2") (pintype "bidirectional"))
    )
    (net (code "45") (name "Net-(E1-SIGNAL)") (class "Default")
      (node (ref "D10") (pin "1") (pinfunction "1_1") (pintype "bidirectional"))
      (node (ref "E1") (pin "SIG") (pinfunction "SIGNAL_SIG") (pintype "bidirectional"))
      (node (ref "FB1") (pin "1") (pinfunction "1_1") (pintype "passive"))
      (node (ref "U11") (pin "P2") (pinfunction "RF_IN_P2") (pintype "input"))
    )
    (net (code "46") (name "Net-(J3-CC1)") (class "Default")
      (node (ref "J3") (pin "A5") (pinfunction "CC1_A5") (pintype "bidirectional"))
      (node (ref "R38") (pin "2") (pinfunction "2_2") (pintype "passive"))
    )
    (net (code "47") (name "Net-(J3-CC2)") (class "Default")
      (node (ref "J3") (pin "B5") (pinfunction "CC2_B5") (pintype "bidirectional"))
      (node (ref "R37") (pin "2") (pinfunction "2_2") (pintype "passive"))
    )
    (net (code "48") (name "Net-(J5-CC1)") (class "Default")
      (node (ref "J5") (pin "A5") (pinfunction "CC1_A5") (pintype "bidirectional"))
      (node (ref "R17") (pin "2") (pinfunction "2_2") (pintype "passive"))
    )
    (net (code "49") (name "Net-(J5-CC2)") (class "Default")
      (node (ref "J5") (pin "B5") (pinfunction "CC2_B5") (pintype "bidirectional"))
      (node (ref "R16") (pin "2") (pinfunction "2_2") (pintype "passive"))
    )
    (net (code "50") (name "Net-(J5-VBUS-PadVBUS1)") (class "Default")
      (node (ref "J5") (pin "VBUS1") (pinfunction "VBUS_VBUS1") (pintype "bidirectional"))
      (node (ref "J5") (pin "VBUS2") (pinfunction "VBUS_VBUS2") (pintype "bidirectional"))
      (node (ref "MEAS") (pin "1") (pinfunction "1_1") (pintype "passive"))
      (node (ref "MEAS") (pin "3") (pinfunction "1_3") (pintype "passive"))
    )
    (net (code "51") (name "Net-(J8-+)") (class "Default")
      (node (ref "J8") (pin "2") (pinfunction "+_2") (pintype "bidirectional"))
      (node (ref "MEAS1") (pin "1") (pinfunction "1_1") (pintype "passive"))
      (node (ref "MEAS1") (pin "3") (pinfunction "1_3") (pintype "passive"))
    )
    (net (code "52") (name "Net-(Q1A-D)") (class "Default")
      (node (ref "C22") (pin "1") (pinfunction "1_1") (pintype "passive"))
      (node (ref "C23") (pin "2") (pinfunction "2_2") (pintype "passive"))
      (node (ref "Q1") (pin "D1") (pinfunction "D_D1") (pintype "bidirectional"))
      (node (ref "Q1") (pin "G2") (pinfunction "G_G2") (pintype "bidirectional"))
      (node (ref "R26") (pin "1") (pinfunction "1_1") (pintype "passive"))
    )
    (net (code "53") (name "Net-(Q2A-B)") (class "Default")
      (node (ref "Q2") (pin "5") (pinfunction "B_5") (pintype "passive"))
      (node (ref "R23") (pin "2") (pinfunction "2_2") (pintype "passive"))
    )
    (net (code "54") (name "Net-(Q2A-E)") (class "Default")
      (node (ref "Q2") (pin "4") (pinfunction "E_4") (pintype "passive"))
      (node (ref "R29") (pin "1") (pinfunction "1_1") (pintype "passive"))
      (node (ref "U6") (pin "14") (pinfunction "~{RTS}_14") (pintype "bidirectional"))
    )
    (net (code "55") (name "Net-(Q2B-B)") (class "Default")
      (node (ref "Q2") (pin "2") (pinfunction "B_2") (pintype "passive"))
      (node (ref "R29") (pin "2") (pinfunction "2_2") (pintype "passive"))
    )
    (net (code "56") (name "Net-(Q2B-E)") (class "Default")
      (node (ref "Q2") (pin "1") (pinfunction "E_1") (pintype "passive"))
      (node (ref "R23") (pin "1") (pinfunction "1_1") (pintype "passive"))
      (node (ref "U6") (pin "13") (pinfunction "~{DTR}_13") (pintype "bidirectional"))
    )
    (net (code "57") (name "Net-(R2A-1)") (class "Default")
      (node (ref "R2") (pin "P1") (pinfunction "1_P1") (pintype "passive"))
      (node (ref "U11") (pin "P45") (pinfunction "SCL/CLK_P45") (pintype "bidirectional"))
    )
    (net (code "58") (name "Net-(R2B-1)") (class "Default")
      (node (ref "R2") (pin "P2") (pinfunction "1_P2") (pintype "passive"))
      (node (ref "U11") (pin "P44") (pinfunction "SDA/~{CS}_P44") (pintype "bidirectional"))
    )
    (net (code "59") (name "Net-(R2C-1)") (class "Default")
      (node (ref "R2") (pin "P3") (pinfunction "1_P3") (pintype "passive"))
      (node (ref "U11") (pin "P43") (pinfunction "RX/MOSI_P43") (pintype "bidirectional"))
    )
    (net (code "60") (name "Net-(R2D-1)") (class "Default")
      (node (ref "R2") (pin "P4") (pinfunction "1_P4") (pintype "passive"))
      (node (ref "U11") (pin "P42") (pinfunction "TX/MISO_P42") (pintype "bidirectional"))
    )
    (net (code "61") (name "Net-(R3A-1)") (class "Default")
      (node (ref "R3") (pin "P1") (pinfunction "1_P1") (pintype "passive"))
      (node (ref "U11") (pin "P50") (pinfunction "~{SAFEBOOT}_P50") (pintype "input"))
    )
    (net (code "62") (name "Net-(R3B-1)") (class "Default")
      (node (ref "R3") (pin "P2") (pinfunction "1_P2") (pintype "passive"))
      (node (ref "U11") (pin "P49") (pinfunction "~{RESET}_P49") (pintype "bidirectional"))
    )
    (net (code "63") (name "Net-(R3C-1)") (class "Default")
      (node (ref "R3") (pin "P3") (pinfunction "1_P3") (pintype "passive"))
      (node (ref "U11") (pin "P47") (pinfunction "D_SEL_P47") (pintype "bidirectional"))
    )
    (net (code "64") (name "Net-(R3D-1)") (class "Default")
      (node (ref "R3") (pin "P4") (pinfunction "1_P4") (pintype "passive"))
      (node (ref "U11") (pin "P46") (pinfunction "TX_READY_P46") (pintype "bidirectional"))
    )
    (net (code "65") (name "Net-(R4A-1)") (class "Default")
      (node (ref "R4") (pin "P1") (pinfunction "1_P1") (pintype "passive"))
      (node (ref "U11") (pin "P27") (pinfunction "TX2_P27") (pintype "output"))
    )
    (net (code "66") (name "Net-(R4B-1)") (class "Default")
      (node (ref "R4") (pin "P2") (pinfunction "1_P2") (pintype "passive"))
      (node (ref "U11") (pin "P26") (pinfunction "RX2_P26") (pintype "input"))
    )
    (net (code "67") (name "Net-(R4C-1)") (class "Default")
      (node (ref "R4") (pin "P3") (pinfunction "1_P3") (pintype "passive"))
      (node (ref "U11") (pin "P23") (pinfunction "DIR_P23") (pintype "input"))
    )
    (net (code "68") (name "Net-(R4D-1)") (class "Default")
      (node (ref "R4") (pin "P4") (pinfunction "1_P4") (pintype "passive"))
      (node (ref "U11") (pin "P22") (pinfunction "WHEEL_TKS_P22") (pintype "input"))
    )
    (net (code "69") (name "Net-(R9A-1)") (class "Default")
      (node (ref "R9") (pin "P1") (pinfunction "1_P1") (pintype "passive"))
      (node (ref "U11") (pin "P53") (pinfunction "TIMEPULSE_P53") (pintype "output"))
    )
    (net (code "70") (name "Net-(R9B-1)") (class "Default")
      (node (ref "R9") (pin "P2") (pinfunction "1_P2") (pintype "passive"))
      (node (ref "U11") (pin "P51") (pinfunction "EXTINT_P51") (pintype "bidirectional"))
    )
    (net (code "71") (name "Net-(R18-Pad2)") (class "Default")
      (node (ref "R18") (pin "2") (pinfunction "2_2") (pintype "bidirectional"))
      (node (ref "R30") (pin "2") (pinfunction "2_2") (pintype "passive"))
      (node (ref "R5") (pin "2") (pinfunction "2_2") (pintype "passive"))
    )
    (net (code "72") (name "Net-(R25C-2)") (class "Default")
      (node (ref "R25") (pin "P6") (pinfunction "2_P6") (pintype "passive"))
      (node (ref "U11") (pin "P19") (pinfunction "GEO_FENCE_STAT_P19") (pintype "output"))
    )
    (net (code "73") (name "Net-(R25D-2)") (class "Default")
      (node (ref "R25") (pin "P5") (pinfunction "2_P5") (pintype "passive"))
      (node (ref "U11") (pin "P20") (pinfunction "RTK_STAT_P20") (pintype "output"))
    )
    (net (code "74") (name "Net-(U5-IO17)") (class "Default")
      (node (ref "R19") (pin "1") (pinfunction "1_1") (pintype "passive"))
      (node (ref "U5") (pin "28") (pinfunction "IO17_28") (pintype "bidirectional"))
    )
    (net (code "75") (name "Net-(U6-UD+)") (class "Default")
      (node (ref "D2") (pin "4") (pinfunction "4_4") (pintype "bidirectional"))
      (node (ref "U6") (pin "5") (pinfunction "UD+_5") (pintype "bidirectional"))
    )
    (net (code "76") (name "Net-(U6-UD-)") (class "Default")
      (node (ref "D2") (pin "6") (pinfunction "6_6") (pintype "bidirectional"))
      (node (ref "U6") (pin "6") (pinfunction "UD-_6") (pintype "bidirectional"))
    )
    (net (code "77") (name "Net-(U10-PROG)") (class "Default")
      (node (ref "R7") (pin "2") (pinfunction "2_2") (pintype "passive"))
      (node (ref "U10") (pin "6") (pinfunction "PROG_6") (pintype "bidirectional"))
    )
    (net (code "78") (name "Net-(U10-THERM)") (class "Default")
      (node (ref "R5") (pin "1") (pinfunction "1_1") (pintype "passive"))
      (node (ref "U10") (pin "8") (pinfunction "THERM_8") (pintype "bidirectional"))
    )
    (net (code "79") (name "Net-(U11-USB_D+)") (class "Default")
      (node (ref "R27") (pin "2") (pinfunction "2_2") (pintype "passive"))
      (node (ref "U11") (pin "P40") (pinfunction "USB_D+_P40") (pintype "bidirectional"))
    )
    (net (code "80") (name "Net-(U11-USB_D-)") (class "Default")
      (node (ref "R28") (pin "2") (pinfunction "2_2") (pintype "passive"))
      (node (ref "U11") (pin "P39") (pinfunction "USB_D-_P39") (pintype "bidirectional"))
    )
    (net (code "81") (name "Net-(U11-V_RF)") (class "Default")
      (node (ref "R14") (pin "2") (pinfunction "2_2") (pintype "passive"))
      (node (ref "U11") (pin "P7") (pinfunction "V_RF_P7") (pintype "output"))
    )
    (net (code "82") (name "POWER_BTN") (class "Default")
      (node (ref "C23") (pin "1") (pinfunction "1_1") (pintype "passive"))
      (node (ref "D1") (pin "C") (pinfunction "C_C") (pintype "passive"))
      (node (ref "J19") (pin "5") (pinfunction "5_5") (pintype "passive"))
      (node (ref "J7") (pin "4") (pinfunction "4_4") (pintype "passive"))
      (node (ref "JP1") (pin "2") (pinfunction "2_2") (pintype "passive"))
      (node (ref "R31") (pin "1") (pinfunction "1_1") (pintype "passive"))
    )
    (net (code "83") (name "VOUT") (class "Default")
      (node (ref "C20") (pin "1") (pinfunction "1_1") (pintype "passive"))
      (node (ref "C6") (pin "1") (pinfunction "1_1") (pintype "passive"))
      (node (ref "J11") (pin "4") (pinfunction "4_4") (pintype "passive"))
      (node (ref "J9") (pin "1") (pinfunction "1_1") (pintype "passive"))
      (node (ref "Q1") (pin "D2") (pinfunction "D_D2") (pintype "bidirectional"))
      (node (ref "R22") (pin "2") (pinfunction "2_2") (pintype "passive"))
      (node (ref "U2") (pin "1") (pinfunction "IN_1") (pintype "input"))
      (node (ref "U2") (pin "3") (pinfunction "EN_3") (pintype "input"))
    )
    (net (code "84") (name "V_BATT") (class "Default")
      (node (ref "C15") (pin "1") (pinfunction "1_1") (pintype "passive"))
      (node (ref "C17") (pin "1") (pinfunction "1_1") (pintype "passive"))
      (node (ref "C8") (pin "1") (pinfunction "1_1") (pintype "passive"))
      (node (ref "D7") (pin "A") (pinfunction "A_A") (pintype "passive"))
      (node (ref "J10") (pin "1") (pinfunction "1_1") (pintype "passive"))
      (node (ref "MEAS1") (pin "2") (pinfunction "2_2") (pintype "passive"))
      (node (ref "MEAS1") (pin "4") (pinfunction "2_4") (pintype "passive"))
      (node (ref "U10") (pin "10") (pinfunction "VBAT_10") (pintype "bidirectional"))
      (node (ref "U10") (pin "9") (pinfunction "VBAT_9") (pintype "bidirectional"))
      (node (ref "U4") (pin "1") (pinfunction "IN_1") (pintype "input"))
      (node (ref "U4") (pin "3") (pinfunction "EN_3") (pintype "input"))
      (node (ref "U7") (pin "2") (pinfunction "CELL_2") (pintype "input"))
      (node (ref "U7") (pin "3") (pinfunction "VDD_3") (pintype "bidirectional"))
    )
    (net (code "85") (name "V_BKCP") (class "Default")
      (node (ref "C18") (pin "1") (pinfunction "1_1") (pintype "passive"))
      (node (ref "U11") (pin "P36") (pinfunction "V_BKCP_P36") (pintype "power_in"))
      (node (ref "U4") (pin "5") (pinfunction "OUT_5") (pintype "passive"))
    )
    (net (code "86") (name "V_RAW") (class "Default")
      (node (ref "C22") (pin "2") (pinfunction "2_2") (pintype "passive"))
      (node (ref "C9") (pin "1") (pinfunction "1_1") (pintype "passive"))
      (node (ref "D3") (pin "C") (pinfunction "C_C") (pintype "passive"))
      (node (ref "D7") (pin "C") (pinfunction "C_C") (pintype "passive"))
      (node (ref "Q1") (pin "S2") (pinfunction "S_S2") (pintype "bidirectional"))
      (node (ref "R26") (pin "2") (pinfunction "2_2") (pintype "passive"))
      (node (ref "R31") (pin "2") (pinfunction "2_2") (pintype "passive"))
      (node (ref "U10") (pin "1") (pinfunction "VDD_1") (pintype "bidirectional"))
      (node (ref "U10") (pin "2") (pinfunction "VDD_2") (pintype "bidirectional"))
    )
    (net (code "87") (name "V_USB") (class "Default")
      (node (ref "D2") (pin "5") (pinfunction "5_5") (pintype "power_in"))
      (node (ref "D3") (pin "A") (pinfunction "A_A") (pintype "passive"))
      (node (ref "D6") (pin "5") (pinfunction "5_5") (pintype "power_in"))
      (node (ref "D9") (pin "C") (pinfunction "C_C") (pintype "passive"))
      (node (ref "J19") (pin "1") (pinfunction "1_1") (pintype "passive"))
      (node (ref "MEAS") (pin "2") (pinfunction "2_2") (pintype "passive"))
      (node (ref "MEAS") (pin "4") (pinfunction "2_4") (pintype "passive"))
    )
    (net (code "88") (name "ZED-RXI2") (class "Default")
      (node (ref "J11") (pin "2") (pinfunction "2_2") (pintype "passive"))
      (node (ref "J9") (pin "3") (pinfunction "3_3") (pintype "passive"))
      (node (ref "R4") (pin "P7") (pinfunction "2_P7") (pintype "passive"))
    )
    (net (code "89") (name "ZED-TXO2") (class "Default")
      (node (ref "J11") (pin "3") (pinfunction "3_3") (pintype "passive"))
      (node (ref "J9") (pin "2") (pinfunction "2_2") (pintype "passive"))
      (node (ref "R4") (pin "P8") (pinfunction "2_P8") (pintype "passive"))
    )
    (net (code "90") (name "ZED_DIR") (class "Default")
      (node (ref "R4") (pin "P6") (pinfunction "2_P6") (pintype "passive"))
      (node (ref "U9") (pin "P4") (pinfunction "Y_P4") (pintype "output"))
    )
    (net (code "91") (name "ZED_D_SEL") (class "Default")
      (node (ref "J6") (pin "2") (pinfunction "2_2") (pintype "passive"))
      (node (ref "R3") (pin "P6") (pinfunction "2_P6") (pintype "passive"))
    )
    (net (code "92") (name "ZED_EXTINT") (class "Default")
      (node (ref "R9") (pin "P7") (pinfunction "2_P7") (pintype "passive"))
      (node (ref "U1") (pin "5") (pinfunction "Y1_5") (pintype "bidirectional"))
    )
    (net (code "93") (name "ZED_FENCE_STAT") (class "Default")
      (node (ref "J1") (pin "1") (pinfunction "1_1") (pintype "passive"))
      (node (ref "R25") (pin "P3") (pinfunction "1_P3") (pintype "passive"))
    )
    (net (code "94") (name "ZED_PPS_STAT") (class "Default")
      (node (ref "J6") (pin "5") (pinfunction "5_5") (pintype "passive"))
      (node (ref "R9") (pin "P8") (pinfunction "2_P8") (pintype "passive"))
      (node (ref "U1") (pin "14") (pinfunction "X1_14") (pintype "bidirectional"))
    )
    (net (code "95") (name "ZED_RTK_STAT") (class "Default")
      (node (ref "J1") (pin "2") (pinfunction "2_2") (pintype "passive"))
      (node (ref "R25") (pin "P4") (pinfunction "1_P4") (pintype "passive"))
    )
    (net (code "96") (name "ZED_WT") (class "Default")
      (node (ref "R4") (pin "P5") (pinfunction "2_P5") (pintype "passive"))
      (node (ref "U8") (pin "P4") (pinfunction "Y_P4") (pintype "output"))
    )
    (net (code "97") (name "ZED_~{RESET}") (class "Default")
      (node (ref "J6") (pin "3") (pinfunction "3_3") (pintype "passive"))
      (node (ref "R3") (pin "P7") (pinfunction "2_P7") (pintype "passive"))
    )
    (net (code "98") (name "ZED_~{SAFE}") (class "Default")
      (node (ref "J6") (pin "4") (pinfunction "4_4") (pintype "passive"))
      (node (ref "R3") (pin "P8") (pinfunction "2_P8") (pintype "passive"))
    )
    (net (code "99") (name "unconnected-(J8-PAD1-PadNC1)") (class "Default")
      (node (ref "J8") (pin "NC1") (pinfunction "PAD1_NC1") (pintype "bidirectional"))
    )
    (net (code "100") (name "unconnected-(J8-PAD2-PadNC2)") (class "Default")
      (node (ref "J8") (pin "NC2") (pinfunction "PAD2_NC2") (pintype "bidirectional"))
    )
    (net (code "101") (name "unconnected-(J16-DAT1-Pad8)") (class "Default")
      (node (ref "J16") (pin "8") (pinfunction "DAT1_8") (pintype "bidirectional"))
    )
    (net (code "102") (name "unconnected-(J16-DAT2-Pad1)") (class "Default")
      (node (ref "J16") (pin "1") (pinfunction "DAT2_1") (pintype "bidirectional"))
    )
    (net (code "103") (name "unconnected-(J16-DET-Pad9)") (class "Default")
      (node (ref "J16") (pin "9") (pinfunction "DET_9") (pintype "bidirectional"))
    )
    (net (code "104") (name "unconnected-(J19-Pad3)") (class "Default")
      (node (ref "J19") (pin "3") (pinfunction "3_3") (pintype "passive"))
    )
    (net (code "105") (name "unconnected-(U2-NC-Pad4)") (class "Default")
      (node (ref "U2") (pin "4") (pinfunction "NC_4") (pintype "no_connect"))
    )
    (net (code "106") (name "unconnected-(U4-NC-Pad4)") (class "Default")
      (node (ref "U4") (pin "4") (pinfunction "NC_4") (pintype "no_connect"))
    )
    (net (code "107") (name "unconnected-(U6-R232-Pad15)") (class "Default")
      (node (ref "U6") (pin "15") (pinfunction "R232_15") (pintype "bidirectional"))
    )
    (net (code "108") (name "unconnected-(U6-~{CTS}-Pad9)") (class "Default")
      (node (ref "U6") (pin "9") (pinfunction "~{CTS}_9") (pintype "bidirectional"))
    )
    (net (code "109") (name "unconnected-(U6-~{DCD}-Pad12)") (class "Default")
      (node (ref "U6") (pin "12") (pinfunction "~{DCD}_12") (pintype "bidirectional"))
    )
    (net (code "110") (name "unconnected-(U6-~{DSR}-Pad10)") (class "Default")
      (node (ref "U6") (pin "10") (pinfunction "~{DSR}_10") (pintype "bidirectional"))
    )
    (net (code "111") (name "unconnected-(U6-~{RI}-Pad11)") (class "Default")
      (node (ref "U6") (pin "11") (pinfunction "~{RI}_11") (pintype "bidirectional"))
    )
    (net (code "112") (name "unconnected-(U7-~{ALRT}-Pad5)") (class "Default")
      (node (ref "U7") (pin "5") (pinfunction "~{ALRT}_5") (pintype "bidirectional"))
    )
    (net (code "113") (name "unconnected-(U10-STAT2-Pad4)") (class "Default")
      (node (ref "U10") (pin "4") (pinfunction "STAT2_4") (pintype "bidirectional"))
    )
    (net (code "114") (name "unconnected-(U10-~{PG}-Pad7)") (class "Default")
      (node (ref "U10") (pin "7") (pinfunction "~{PG}_7") (pintype "bidirectional"))
    )
    (net (code "115") (name "unconnected-(U11-ANT_DETECT-PadP4)") (class "Default")
      (node (ref "U11") (pin "P4") (pinfunction "ANT_DETECT_P4") (pintype "input"))
    )
    (net (code "116") (name "unconnected-(U11-ANT_OFF-PadP5)") (class "Default")
      (node (ref "U11") (pin "P5") (pinfunction "ANT_OFF_P5") (pintype "output"))
    )
    (net (code "117") (name "unconnected-(U11-RSVD-PadP8)") (class "Default")
      (node (ref "U11") (pin "P8") (pinfunction "RSVD_P8") (pintype "no_connect"))
    )
    (net (code "118") (name "unconnected-(U11-RSVD-PadP9)") (class "Default")
      (node (ref "U11") (pin "P9") (pinfunction "RSVD_P9") (pintype "no_connect"))
    )
    (net (code "119") (name "unconnected-(U11-RSVD-PadP10)") (class "Default")
      (node (ref "U11") (pin "P10") (pinfunction "RSVD_P10") (pintype "no_connect"))
    )
    (net (code "120") (name "unconnected-(U11-RSVD-PadP11)") (class "Default")
      (node (ref "U11") (pin "P11") (pinfunction "RSVD_P11") (pintype "no_connect"))
    )
    (net (code "121") (name "unconnected-(U11-RSVD-PadP13)") (class "Default")
      (node (ref "U11") (pin "P13") (pinfunction "RSVD_P13") (pintype "no_connect"))
    )
    (net (code "122") (name "unconnected-(U11-RSVD-PadP15)") (class "Default")
      (node (ref "U11") (pin "P15") (pinfunction "RSVD_P15") (pintype "no_connect"))
    )
    (net (code "123") (name "unconnected-(U11-RSVD-PadP16)") (class "Default")
      (node (ref "U11") (pin "P16") (pinfunction "RSVD_P16") (pintype "no_connect"))
    )
    (net (code "124") (name "unconnected-(U11-RSVD-PadP17)") (class "Default")
      (node (ref "U11") (pin "P17") (pinfunction "RSVD_P17") (pintype "no_connect"))
    )
    (net (code "125") (name "unconnected-(U11-RSVD-PadP18)") (class "Default")
      (node (ref "U11") (pin "P18") (pinfunction "RSVD_P18") (pintype "no_connect"))
    )
    (net (code "126") (name "unconnected-(U11-RSVD-PadP21)") (class "Default")
      (node (ref "U11") (pin "P21") (pinfunction "RSVD_P21") (pintype "no_connect"))
    )
    (net (code "127") (name "unconnected-(U11-RSVD-PadP24)") (class "Default")
      (node (ref "U11") (pin "P24") (pinfunction "RSVD_P24") (pintype "no_connect"))
    )
    (net (code "128") (name "unconnected-(U11-RSVD-PadP25)") (class "Default")
      (node (ref "U11") (pin "P25") (pinfunction "RSVD_P25") (pintype "no_connect"))
    )
    (net (code "129") (name "unconnected-(U11-RSVD-PadP28)") (class "Default")
      (node (ref "U11") (pin "P28") (pinfunction "RSVD_P28") (pintype "no_connect"))
    )
    (net (code "130") (name "unconnected-(U11-RSVD-PadP29)") (class "Default")
      (node (ref "U11") (pin "P29") (pinfunction "RSVD_P29") (pintype "no_connect"))
    )
    (net (code "131") (name "unconnected-(U11-RSVD-PadP30)") (class "Default")
      (node (ref "U11") (pin "P30") (pinfunction "RSVD_P30") (pintype "no_connect"))
    )
    (net (code "132") (name "unconnected-(U11-RSVD-PadP31)") (class "Default")
      (node (ref "U11") (pin "P31") (pinfunction "RSVD_P31") (pintype "no_connect"))
    )
    (net (code "133") (name "unconnected-(U11-RSVD-PadP35)") (class "Default")
      (node (ref "U11") (pin "P35") (pinfunction "RSVD_P35") (pintype "no_connect"))
    )
    (net (code "134") (name "unconnected-(U11-RSVD-PadP52)") (class "Default")
      (node (ref "U11") (pin "P52") (pinfunction "RSVD_P52") (pintype "no_connect"))
    )
    (net (code "135") (name "unconnected-(U11-RSVD-PadP54)") (class "Default")
      (node (ref "U11") (pin "P54") (pinfunction "RSVD_P54") (pintype "no_connect"))
    )
    (net (code "136") (name "unconnected-(U11-~{ANT_SHORT}-PadP6)") (class "Default")
      (node (ref "U11") (pin "P6") (pinfunction "~{ANT_SHORT}_P6") (pintype "output"))
    )
    (net (code "137") (name "unconnected-(U13-INT2-Pad11)") (class "Default")
      (node (ref "U13") (pin "11") (pinfunction "INT2_11") (pintype "bidirectional"))
    )
  )
)
